# polulu.net
KiCad netlist of a schematic drawn in EAGLE
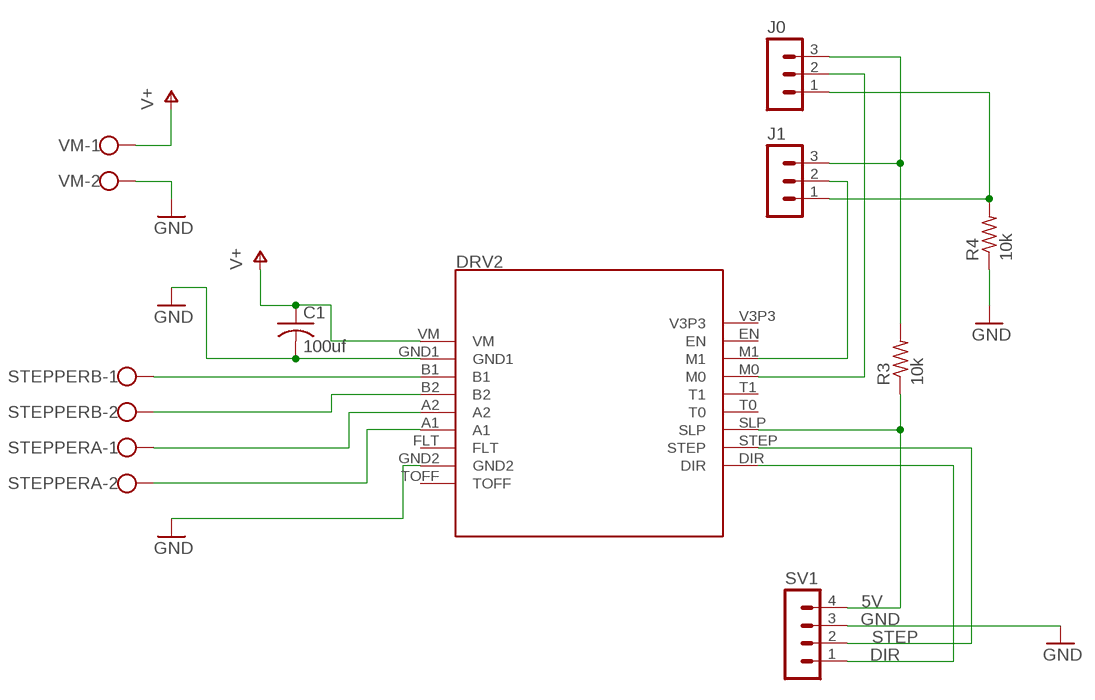
[diagram p0: schematic, sheet 1]

(export (version "E")
  (design (tool "Eeschema 10.0.6"))
  (components
    (comp (ref "C1")
      (value "100uf")
      (footprint "eagle-import:C025-024X044")
      (libsource (lib "eagle-import") (part "C-US025-024X044"))
    )
    (comp (ref "DRV2")
      (value "DRV8880")
      (footprint "eagle-import:DRV8880")
      (libsource (lib "eagle-import") (part "DRV8880"))
    )
    (comp (ref "J0")
      (value "MA03-1")
      (footprint "eagle-import:MA03-1")
      (libsource (lib "eagle-import") (part "MA03-1"))
    )
    (comp (ref "J1")
      (value "MA03-1")
      (footprint "eagle-import:MA03-1")
      (libsource (lib "eagle-import") (part "MA03-1"))
    )
    (comp (ref "R3")
      (value "10k")
      (footprint "eagle-import:0204_7")
      (libsource (lib "eagle-import") (part "R-US_0204/7"))
    )
    (comp (ref "R4")
      (value "10k")
      (footprint "eagle-import:0204_7")
      (libsource (lib "eagle-import") (part "R-US_0204/7"))
    )
    (comp (ref "STEPPERA")
      (value "W237-102")
      (footprint "eagle-import:W237-102")
      (fields (field (name "MPN") "237-102"))
      (libsource (lib "eagle-import") (part "W237-102"))
    )
    (comp (ref "STEPPERB")
      (value "W237-102")
      (footprint "eagle-import:W237-102")
      (fields (field (name "MPN") "237-102"))
      (libsource (lib "eagle-import") (part "W237-102"))
    )
    (comp (ref "SV1")
      (value "MA04-1")
      (footprint "eagle-import:MA04-1")
      (libsource (lib "eagle-import") (part "MA04-1"))
    )
    (comp (ref "VM")
      (value "W237-102")
      (footprint "eagle-import:W237-102")
      (fields (field (name "MPN") "237-102"))
      (libsource (lib "eagle-import") (part "W237-102"))
    )
  )
  (nets
    (net (code "1") (name "/5V") (class "Default")
      (node (ref "DRV2") (pin "SLP") (pinfunction "SLP_SLP") (pintype "bidirectional"))
      (node (ref "R3") (pin "1") (pinfunction "1_1") (pintype "passive"))
      (node (ref "SV1") (pin "4") (pinfunction "4_4") (pintype "passive"))
    )
    (net (code "2") (name "/DIR") (class "Default")
      (node (ref "DRV2") (pin "DIR") (pinfunction "DIR_DIR") (pintype "bidirectional"))
      (node (ref "SV1") (pin "1") (pinfunction "1_1") (pintype "passive"))
    )
    (net (code "3") (name "/STEP") (class "Default")
      (node (ref "DRV2") (pin "STEP") (pinfunction "STEP_STEP") (pintype "bidirectional"))
      (node (ref "SV1") (pin "2") (pinfunction "2_2") (pintype "passive"))
    )
    (net (code "4") (name "GND") (class "Default")
      (node (ref "C1") (pin "2") (pinfunction "2_2") (pintype "passive"))
      (node (ref "DRV2") (pin "GND1") (pinfunction "GND1_GND1") (pintype "bidirectional"))
      (node (ref "DRV2") (pin "GND2") (pinfunction "GND2_GND2") (pintype "bidirectional"))
      (node (ref "R4") (pin "1") (pinfunction "1_1") (pintype "passive"))
      (node (ref "SV1") (pin "3") (pinfunction "3_3") (pintype "passive"))
      (node (ref "VM") (pin "2") (pinfunction "KL_2") (pintype "passive"))
    )
    (net (code "5") (name "Net-(DRV2-PadM0)") (class "Default")
      (node (ref "DRV2") (pin "M0") (pinfunction "M0_M0") (pintype "bidirectional"))
      (node (ref "J0") (pin "2") (pinfunction "2_2") (pintype "passive"))
    )
    (net (code "6") (name "Net-(DRV2-PadM1)") (class "Default")
      (node (ref "DRV2") (pin "M1") (pinfunction "M1_M1") (pintype "bidirectional"))
      (node (ref "J1") (pin "2") (pinfunction "2_2") (pintype "passive"))
    )
    (net (code "7") (name "Net-(J0-Pad1)") (class "Default")
      (node (ref "J0") (pin "1") (pinfunction "1_1") (pintype "passive"))
      (node (ref "J1") (pin "1") (pinfunction "1_1") (pintype "passive"))
      (node (ref "R4") (pin "2") (pinfunction "2_2") (pintype "passive"))
    )
    (net (code "8") (name "Net-(J0-Pad3)") (class "Default")
      (node (ref "J0") (pin "3") (pinfunction "3_3") (pintype "passive"))
      (node (ref "J1") (pin "3") (pinfunction "3_3") (pintype "passive"))
      (node (ref "R3") (pin "2") (pinfunction "2_2") (pintype "passive"))
    )
    (net (code "9") (name "Net-(STEPPERAA-KL)") (class "Default")
      (node (ref "DRV2") (pin "A2") (pinfunction "A2_A2") (pintype "bidirectional"))
      (node (ref "STEPPERA") (pin "1") (pinfunction "KL_1") (pintype "passive"))
    )
    (net (code "10") (name "Net-(STEPPERAB-KL)") (class "Default")
      (node (ref "DRV2") (pin "A1") (pinfunction "A1_A1") (pintype "bidirectional"))
      (node (ref "STEPPERA") (pin "2") (pinfunction "KL_2") (pintype "passive"))
    )
    (net (code "11") (name "Net-(STEPPERBA-KL)") (class "Default")
      (node (ref "DRV2") (pin "B1") (pinfunction "B1_B1") (pintype "bidirectional"))
      (node (ref "STEPPERB") (pin "1") (pinfunction "KL_1") (pintype "passive"))
    )
    (net (code "12") (name "Net-(STEPPERBB-KL)") (class "Default")
      (node (ref "DRV2") (pin "B2") (pinfunction "B2_B2") (pintype "bidirectional"))
      (node (ref "STEPPERB") (pin "2") (pinfunction "KL_2") (pintype "passive"))
    )
    (net (code "13") (name "V+") (class "Default")
      (node (ref "C1") (pin "1") (pinfunction "1_1") (pintype "passive"))
      (node (ref "DRV2") (pin "VM") (pinfunction "VM_VM") (pintype "bidirectional"))
      (node (ref "VM") (pin "1") (pinfunction "KL_1") (pintype "passive"))
    )
    (net (code "14") (name "unconnected-(DRV2-PadEN)") (class "Default")
      (node (ref "DRV2") (pin "EN") (pinfunction "EN_EN") (pintype "bidirectional"))
    )
    (net (code "15") (name "unconnected-(DRV2-PadFLT)") (class "Default")
      (node (ref "DRV2") (pin "FLT") (pinfunction "FLT_FLT") (pintype "bidirectional"))
    )
    (net (code "16") (name "unconnected-(DRV2-PadT0)") (class "Default")
      (node (ref "DRV2") (pin "T0") (pinfunction "T0_T0") (pintype "bidirectional"))
    )
    (net (code "17") (name "unconnected-(DRV2-PadT1)") (class "Default")
      (node (ref "DRV2") (pin "T1") (pinfunction "T1_T1") (pintype "bidirectional"))
    )
    (net (code "18") (name "unconnected-(DRV2-PadTOFF)") (class "Default")
      (node (ref "DRV2") (pin "TOFF") (pinfunction "TOFF_TOFF") (pintype "bidirectional"))
    )
    (net (code "19") (name "unconnected-(DRV2-PadV3P3)") (class "Default")
      (node (ref "DRV2") (pin "V3P3") (pinfunction "V3P3_V3P3") (pintype "bidirectional"))
    )
  )
)
